# sensor_calibration_board.net
KiCad netlist of a schematic drawn in EAGLE
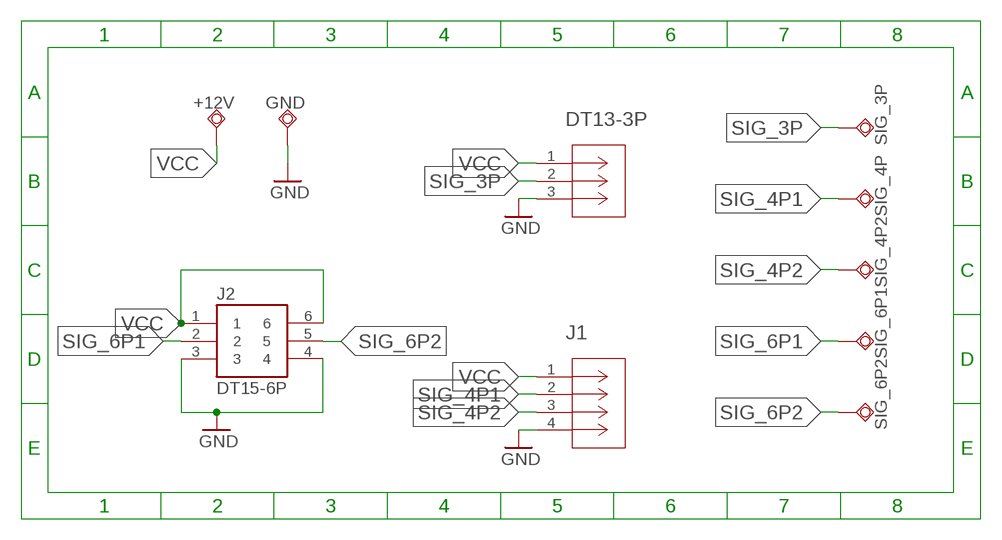
[diagram p0: schematic, sheet 1]

(export (version "E")
  (design (tool "Eeschema 10.0.6"))
  (components
    (comp (ref "+12V")
      (value "TPSQPAD1-20Y")
      (footprint "eagle-import:P1-20Y")
      (libsource (lib "eagle-import") (part "TPSQPAD1-20Y"))
    )
    (comp (ref "DT13-3P")
      (value "DTF13-3P")
      (footprint "eagle-import:CONN3_DTF13-3P")
      (fields (field (name "COPYRIGHT") "Copyright (C) 2016 Accelerated Designs. All rights reserved"))
      (libsource (lib "eagle-import") (part "DTF13-3P"))
    )
    (comp (ref "GND")
      (value "TPSQPAD1-20Y")
      (footprint "eagle-import:P1-20Y")
      (libsource (lib "eagle-import") (part "TPSQPAD1-20Y"))
    )
    (comp (ref "J1")
      (value "DT15-4P-G003S")
      (footprint "eagle-import:CONN4_DT15-4P-G003")
      (fields
        (field (name "MANUFACTURER_PART_NUMBER") "DT15-4P-G003")
        (field (name "COPYRIGHT") "Copyright (C) 2018 Accelerated Designs. All rights reserved")
      )
      (libsource (lib "eagle-import") (part "DT15-4P-G003"))
    )
    (comp (ref "J2")
      (value "DT15-6P")
      (footprint "eagle-import:TE_DT15-6P")
      (fields (field (name "MF") "TE Connectivity"))
      (libsource (lib "eagle-import") (part "DT15-6P"))
    )
    (comp (ref "SIG_3P")
      (value "TPSQPAD1-20Y")
      (footprint "eagle-import:P1-20Y")
      (libsource (lib "eagle-import") (part "TPSQPAD1-20Y"))
    )
    (comp (ref "SIG_4P")
      (value "TPSQPAD1-20Y")
      (footprint "eagle-import:P1-20Y")
      (libsource (lib "eagle-import") (part "TPSQPAD1-20Y"))
    )
    (comp (ref "SIG_4P2")
      (value "TPSQPAD1-20Y")
      (footprint "eagle-import:P1-20Y")
      (libsource (lib "eagle-import") (part "TPSQPAD1-20Y"))
    )
    (comp (ref "SIG_6P1")
      (value "TPSQPAD1-20Y")
      (footprint "eagle-import:P1-20Y")
      (libsource (lib "eagle-import") (part "TPSQPAD1-20Y"))
    )
    (comp (ref "SIG_6P2")
      (value "TPSQPAD1-20Y")
      (footprint "eagle-import:P1-20Y")
      (libsource (lib "eagle-import") (part "TPSQPAD1-20Y"))
    )
  )
  (nets
    (net (code "1") (name "GND") (class "Default")
      (node (ref "DT13-3P") (pin "3") (pinfunction "3_3") (pintype "passive"))
      (node (ref "GND") (pin "1") (pinfunction "TP_1") (pintype "input"))
      (node (ref "J1") (pin "4") (pinfunction "4_4") (pintype "passive"))
      (node (ref "J2") (pin "3") (pinfunction "3_3") (pintype "passive"))
      (node (ref "J2") (pin "4") (pinfunction "4_4") (pintype "passive"))
    )
    (net (code "2") (name "SIG_3P") (class "Default")
      (node (ref "DT13-3P") (pin "2") (pinfunction "2_2") (pintype "passive"))
      (node (ref "SIG_3P") (pin "1") (pinfunction "TP_1") (pintype "input"))
    )
    (net (code "3") (name "SIG_4P1") (class "Default")
      (node (ref "J1") (pin "2") (pinfunction "2_2") (pintype "passive"))
      (node (ref "SIG_4P") (pin "1") (pinfunction "TP_1") (pintype "input"))
    )
    (net (code "4") (name "SIG_4P2") (class "Default")
      (node (ref "J1") (pin "3") (pinfunction "3_3") (pintype "passive"))
      (node (ref "SIG_4P2") (pin "1") (pinfunction "TP_1") (pintype "input"))
    )
    (net (code "5") (name "SIG_6P1") (class "Default")
      (node (ref "J2") (pin "2") (pinfunction "2_2") (pintype "passive"))
      (node (ref "SIG_6P1") (pin "1") (pinfunction "TP_1") (pintype "input"))
    )
    (net (code "6") (name "SIG_6P2") (class "Default")
      (node (ref "J2") (pin "5") (pinfunction "5_5") (pintype "passive"))
      (node (ref "SIG_6P2") (pin "1") (pinfunction "TP_1") (pintype "input"))
    )
    (net (code "7") (name "VCC") (class "Default")
      (node (ref "+12V") (pin "1") (pinfunction "TP_1") (pintype "input"))
      (node (ref "DT13-3P") (pin "1") (pinfunction "1_1") (pintype "passive"))
      (node (ref "J1") (pin "1") (pinfunction "1_1") (pintype "passive"))
      (node (ref "J2") (pin "1") (pinfunction "1_1") (pintype "passive"))
      (node (ref "J2") (pin "6") (pinfunction "6_6") (pintype "passive"))
    )
  )
)
